# REL_IRF_MEZ.net
KiCad netlist of a schematic drawn in Altium Designer
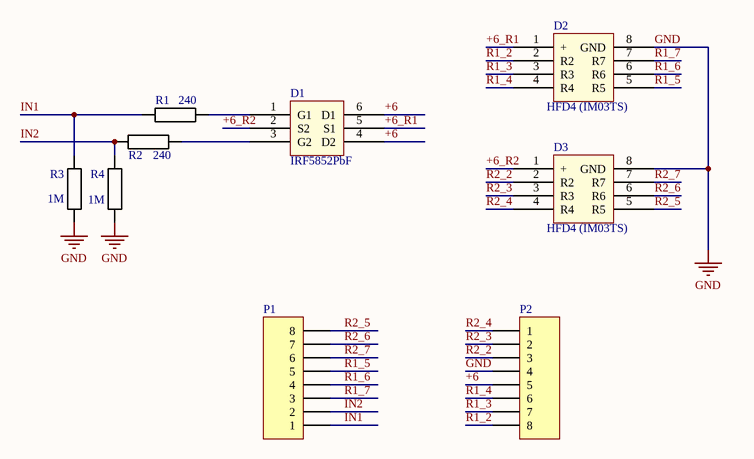
[diagram p0: REL_IRF_MEZ.SchDoc]

(export (version "E")
  (design (tool "Eeschema 10.0.6"))
  (components
    (comp (ref "D1")
      (value "IRF5852PbF")
      (footprint "msp_Active:IRF5852PbF")
      (libsource (lib "msp_SchLib") (part "IRF5852PbF"))
    )
    (comp (ref "D2")
      (value "HFD4 (IM03TS)")
      (footprint "msp_Active:HFD4 (IM03TS)")
      (libsource (lib "msp_SchLib") (part "HFD4 (IM03TS)"))
    )
    (comp (ref "D3")
      (value "HFD4 (IM03TS)")
      (footprint "msp_Active:HFD4 (IM03TS)")
      (libsource (lib "msp_SchLib") (part "HFD4 (IM03TS)"))
    )
    (comp (ref "P1")
      (value "Header 8")
      (footprint "HDR1X8")
      (description "Header, 8-Pin")
      (fields (field (name "PUBLISHER") "Altium Limited"))
      (libsource (lib "Miscellaneous Connectors") (part "Header 8"))
    )
    (comp (ref "P2")
      (value "Header 8")
      (footprint "HDR1X8")
      (description "Header, 8-Pin")
      (fields (field (name "PUBLISHER") "Altium Limited"))
      (libsource (lib "") (part "Header 8_1"))
    )
    (comp (ref "R1")
      (value "240")
      (footprint "aab_Passive:RES_1206")
      (libsource (lib "aab_Schlib") (part "RES"))
    )
    (comp (ref "R2")
      (value "240")
      (footprint "aab_Passive:RES_1206")
      (libsource (lib "aab_Schlib") (part "RES"))
    )
    (comp (ref "R3")
      (value "1М")
      (footprint "aab_Passive:RES_1206")
      (libsource (lib "aab_Schlib") (part "RES"))
    )
    (comp (ref "R4")
      (value "1М")
      (footprint "aab_Passive:RES_1206")
      (libsource (lib "aab_Schlib") (part "RES"))
    )
  )
  (nets
    (net (code "1") (name "/+6") (class "Default")
      (node (ref "D1") (pin "4") (pinfunction "D2_4") (pintype "passive"))
      (node (ref "D1") (pin "6") (pinfunction "D1_6") (pintype "passive"))
      (node (ref "P2") (pin "5") (pinfunction "5_5") (pintype "passive"))
    )
    (net (code "2") (name "/+6_R1") (class "Default")
      (node (ref "D1") (pin "5") (pinfunction "S1_5") (pintype "passive"))
      (node (ref "D2") (pin "1") (pinfunction "+_1") (pintype "passive"))
    )
    (net (code "3") (name "/+6_R2") (class "Default")
      (node (ref "D1") (pin "2") (pinfunction "S2_2") (pintype "passive"))
      (node (ref "D3") (pin "1") (pinfunction "+_1") (pintype "passive"))
    )
    (net (code "4") (name "/IN1") (class "Default")
      (node (ref "P1") (pin "1") (pinfunction "1_1") (pintype "passive"))
      (node (ref "R1") (pin "1") (pinfunction "1_1") (pintype "passive"))
      (node (ref "R3") (pin "1") (pinfunction "1_1") (pintype "passive"))
    )
    (net (code "5") (name "/IN2") (class "Default")
      (node (ref "P1") (pin "2") (pinfunction "2_2") (pintype "passive"))
      (node (ref "R2") (pin "1") (pinfunction "1_1") (pintype "passive"))
      (node (ref "R4") (pin "2") (pinfunction "2_2") (pintype "passive"))
    )
    (net (code "6") (name "/R1_2") (class "Default")
      (node (ref "D2") (pin "2") (pinfunction "R2_2") (pintype "passive"))
      (node (ref "P2") (pin "8") (pinfunction "8_8") (pintype "passive"))
    )
    (net (code "7") (name "/R1_3") (class "Default")
      (node (ref "D2") (pin "3") (pinfunction "R3_3") (pintype "passive"))
      (node (ref "P2") (pin "7") (pinfunction "7_7") (pintype "passive"))
    )
    (net (code "8") (name "/R1_4") (class "Default")
      (node (ref "D2") (pin "4") (pinfunction "R4_4") (pintype "passive"))
      (node (ref "P2") (pin "6") (pinfunction "6_6") (pintype "passive"))
    )
    (net (code "9") (name "/R1_5") (class "Default")
      (node (ref "D2") (pin "5") (pinfunction "R5_5") (pintype "passive"))
      (node (ref "P1") (pin "5") (pinfunction "5_5") (pintype "passive"))
    )
    (net (code "10") (name "/R1_6") (class "Default")
      (node (ref "D2") (pin "6") (pinfunction "R6_6") (pintype "passive"))
      (node (ref "P1") (pin "4") (pinfunction "4_4") (pintype "passive"))
    )
    (net (code "11") (name "/R1_7") (class "Default")
      (node (ref "D2") (pin "7") (pinfunction "R7_7") (pintype "passive"))
      (node (ref "P1") (pin "3") (pinfunction "3_3") (pintype "passive"))
    )
    (net (code "12") (name "/R2_2") (class "Default")
      (node (ref "D3") (pin "2") (pinfunction "R2_2") (pintype "passive"))
      (node (ref "P2") (pin "3") (pinfunction "3_3") (pintype "passive"))
    )
    (net (code "13") (name "/R2_3") (class "Default")
      (node (ref "D3") (pin "3") (pinfunction "R3_3") (pintype "passive"))
      (node (ref "P2") (pin "2") (pinfunction "2_2") (pintype "passive"))
    )
    (net (code "14") (name "/R2_4") (class "Default")
      (node (ref "D3") (pin "4") (pinfunction "R4_4") (pintype "passive"))
      (node (ref "P2") (pin "1") (pinfunction "1_1") (pintype "passive"))
    )
    (net (code "15") (name "/R2_5") (class "Default")
      (node (ref "D3") (pin "5") (pinfunction "R5_5") (pintype "passive"))
      (node (ref "P1") (pin "8") (pinfunction "8_8") (pintype "passive"))
    )
    (net (code "16") (name "/R2_6") (class "Default")
      (node (ref "D3") (pin "6") (pinfunction "R6_6") (pintype "passive"))
      (node (ref "P1") (pin "7") (pinfunction "7_7") (pintype "passive"))
    )
    (net (code "17") (name "/R2_7") (class "Default")
      (node (ref "D3") (pin "7") (pinfunction "R7_7") (pintype "passive"))
      (node (ref "P1") (pin "6") (pinfunction "6_6") (pintype "passive"))
    )
    (net (code "18") (name "GND") (class "Default")
      (node (ref "D2") (pin "8") (pinfunction "GND_8") (pintype "passive"))
      (node (ref "D3") (pin "8") (pinfunction "GND_8") (pintype "passive"))
      (node (ref "P2") (pin "4") (pinfunction "4_4") (pintype "passive"))
      (node (ref "R3") (pin "2") (pinfunction "2_2") (pintype "passive"))
      (node (ref "R4") (pin "1") (pinfunction "1_1") (pintype "passive"))
    )
    (net (code "19") (name "Net-(D1-G1)") (class "Default")
      (node (ref "D1") (pin "1") (pinfunction "G1_1") (pintype "passive"))
      (node (ref "R1") (pin "2") (pinfunction "2_2") (pintype "passive"))
    )
    (net (code "20") (name "Net-(D1-G2)") (class "Default")
      (node (ref "D1") (pin "3") (pinfunction "G2_3") (pintype "passive"))
      (node (ref "R2") (pin "2") (pinfunction "2_2") (pintype "passive"))
    )
  )
)
